# face_board.net
KiCad netlist of a schematic drawn in Altium Designer
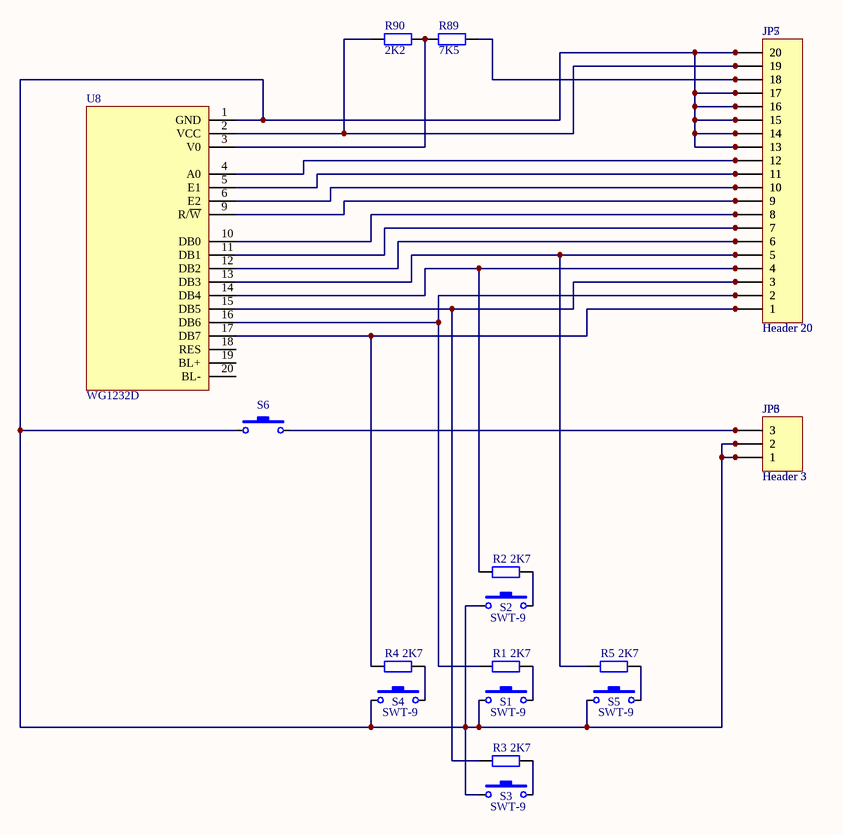
[diagram p0: face_board.SchDoc]

(export (version "E")
  (design (tool "Eeschema 10.0.6"))
  (components
    (comp (ref "JP3")
      (value "Header 3")
      (footprint "HDR1X3")
      (description "Header, 3-Pin")
      (fields (field (name "MANUFACTURER") "Generic Components") (field (name "PUBLISHER") "Altium Limited"))
      (libsource (lib "Miscellaneous Connectors") (part "Header 3"))
    )
    (comp (ref "JP5")
      (value "Header 20")
      (footprint "HDR1X20")
      (description "Header, 20-Pin")
      (fields (field (name "MANUFACTURER") "Generic Components") (field (name "PUBLISHER") "Altium Limited"))
      (libsource (lib "Miscellaneous Connectors") (part "Header 20"))
    )
    (comp (ref "JP6")
      (value "Header 3")
      (footprint "HDR1X3")
      (description "Header, 3-Pin")
      (fields (field (name "MANUFACTURER") "Generic Components") (field (name "PUBLISHER") "Altium Limited"))
      (libsource (lib "Miscellaneous Connectors") (part "Header 3"))
    )
    (comp (ref "JP7")
      (value "Header 20")
      (footprint "HDR1X20")
      (description "Header, 20-Pin")
      (fields (field (name "MANUFACTURER") "Generic Components") (field (name "PUBLISHER") "Altium Limited"))
      (libsource (lib "Miscellaneous Connectors") (part "Header 20"))
    )
    (comp (ref "R1")
      (value "2K7")
      (footprint "_1206")
      (description "Resistor")
      (fields (field (name "MANUFACTURER") "Generic Components") (field (name "PUBLISHER") "Altium Limited"))
      (libsource (lib "Miscellaneous Devices") (part "Res2"))
    )
    (comp (ref "R2")
      (value "2K7")
      (footprint "_1206")
      (description "Resistor")
      (fields (field (name "MANUFACTURER") "Generic Components") (field (name "PUBLISHER") "Altium Limited"))
      (libsource (lib "Miscellaneous Devices") (part "Res2"))
    )
    (comp (ref "R3")
      (value "2K7")
      (footprint "_1206")
      (description "Resistor")
      (fields (field (name "MANUFACTURER") "Generic Components") (field (name "PUBLISHER") "Altium Limited"))
      (libsource (lib "Miscellaneous Devices") (part "Res2"))
    )
    (comp (ref "R4")
      (value "2K7")
      (footprint "_1206")
      (description "Resistor")
      (fields (field (name "MANUFACTURER") "Generic Components") (field (name "PUBLISHER") "Altium Limited"))
      (libsource (lib "Miscellaneous Devices") (part "Res2"))
    )
    (comp (ref "R5")
      (value "2K7")
      (footprint "_1206")
      (description "Resistor")
      (fields (field (name "MANUFACTURER") "Generic Components") (field (name "PUBLISHER") "Altium Limited"))
      (libsource (lib "Miscellaneous Devices") (part "Res2"))
    )
    (comp (ref "R89")
      (value "7K5")
      (footprint "_1206")
      (description "Resistor")
      (fields (field (name "MANUFACTURER") "Generic Components") (field (name "PUBLISHER") "Altium Limited"))
      (libsource (lib "") (part "Res2_1"))
    )
    (comp (ref "R90")
      (value "2K2")
      (footprint "_1206")
      (description "Resistor")
      (fields (field (name "MANUFACTURER") "Generic Components") (field (name "PUBLISHER") "Altium Limited"))
      (libsource (lib "") (part "Res2_1"))
    )
    (comp (ref "S1")
      (value "SWT-9")
      (footprint "SWT-9")
      (description "Switch")
      (fields (field (name "MANUFACTURER") "Generic Components") (field (name "PUBLISHER") "Altium Limited"))
      (libsource (lib "PAL") (part "SWT-9"))
    )
    (comp (ref "S2")
      (value "SWT-9")
      (footprint "SWT-9")
      (description "Switch")
      (fields (field (name "MANUFACTURER") "Generic Components") (field (name "PUBLISHER") "Altium Limited"))
      (libsource (lib "PAL") (part "SWT-9"))
    )
    (comp (ref "S3")
      (value "SWT-9")
      (footprint "SWT-9")
      (description "Switch")
      (fields (field (name "MANUFACTURER") "Generic Components") (field (name "PUBLISHER") "Altium Limited"))
      (libsource (lib "PAL") (part "SWT-9"))
    )
    (comp (ref "S4")
      (value "SWT-9")
      (footprint "SWT-9")
      (description "Switch")
      (fields (field (name "MANUFACTURER") "Generic Components") (field (name "PUBLISHER") "Altium Limited"))
      (libsource (lib "PAL") (part "SWT-9"))
    )
    (comp (ref "S5")
      (value "SWT-9")
      (footprint "SWT-9")
      (description "Switch")
      (fields (field (name "MANUFACTURER") "Generic Components") (field (name "PUBLISHER") "Altium Limited"))
      (libsource (lib "PAL") (part "SWT-9"))
    )
    (comp (ref "S6")
      (value "SWT-6")
      (footprint "SWT-6")
      (description "Button")
      (fields (field (name "MANUFACTURER") "Generic Components") (field (name "PUBLISHER") "Altium Limited"))
      (libsource (lib "PAL") (part "SWT-9"))
    )
    (comp (ref "U8") (value "WG1232D") (footprint "WG1232D") (libsource (lib "PAL") (part "WG1232D_pereh")))
  )
  (nets
    (net (code "1") (name "Net-(JP3-Pad3)") (class "Default")
      (node (ref "JP3") (pin "3") (pinfunction "3_3") (pintype "passive"))
      (node (ref "JP6") (pin "3") (pinfunction "3_3") (pintype "passive"))
      (node (ref "S6") (pin "2") (pinfunction "2_2") (pintype "passive"))
    )
    (net (code "2") (name "Net-(JP5-Pad18)") (class "Default")
      (node (ref "JP5") (pin "18") (pinfunction "18_18") (pintype "passive"))
      (node (ref "JP7") (pin "18") (pinfunction "18_18") (pintype "passive"))
      (node (ref "R89") (pin "1") (pinfunction "1_1") (pintype "passive"))
    )
    (net (code "3") (name "Net-(R1-Pad1)") (class "Default")
      (node (ref "R1") (pin "1") (pinfunction "1_1") (pintype "passive"))
      (node (ref "S1") (pin "2") (pinfunction "2_2") (pintype "passive"))
    )
    (net (code "4") (name "Net-(R2-Pad1)") (class "Default")
      (node (ref "R2") (pin "1") (pinfunction "1_1") (pintype "passive"))
      (node (ref "S2") (pin "2") (pinfunction "2_2") (pintype "passive"))
    )
    (net (code "5") (name "Net-(R3-Pad1)") (class "Default")
      (node (ref "R3") (pin "1") (pinfunction "1_1") (pintype "passive"))
      (node (ref "S3") (pin "2") (pinfunction "2_2") (pintype "passive"))
    )
    (net (code "6") (name "Net-(R4-Pad1)") (class "Default")
      (node (ref "R4") (pin "1") (pinfunction "1_1") (pintype "passive"))
      (node (ref "S4") (pin "2") (pinfunction "2_2") (pintype "passive"))
    )
    (net (code "7") (name "Net-(R5-Pad1)") (class "Default")
      (node (ref "R5") (pin "1") (pinfunction "1_1") (pintype "passive"))
      (node (ref "S5") (pin "2") (pinfunction "2_2") (pintype "passive"))
    )
    (net (code "8") (name "Net-(U8-A0)") (class "Default")
      (node (ref "JP5") (pin "12") (pinfunction "12_12") (pintype "passive"))
      (node (ref "JP7") (pin "12") (pinfunction "12_12") (pintype "passive"))
      (node (ref "U8") (pin "4") (pinfunction "A0_4") (pintype "passive"))
    )
    (net (code "9") (name "Net-(U8-DB0)") (class "Default")
      (node (ref "JP5") (pin "8") (pinfunction "8_8") (pintype "passive"))
      (node (ref "JP7") (pin "8") (pinfunction "8_8") (pintype "passive"))
      (node (ref "U8") (pin "10") (pinfunction "DB0_10") (pintype "passive"))
    )
    (net (code "10") (name "Net-(U8-DB1)") (class "Default")
      (node (ref "JP5") (pin "7") (pinfunction "7_7") (pintype "passive"))
      (node (ref "JP7") (pin "7") (pinfunction "7_7") (pintype "passive"))
      (node (ref "U8") (pin "11") (pinfunction "DB1_11") (pintype "passive"))
    )
    (net (code "11") (name "Net-(U8-DB2)") (class "Default")
      (node (ref "JP5") (pin "6") (pinfunction "6_6") (pintype "passive"))
      (node (ref "JP7") (pin "6") (pinfunction "6_6") (pintype "passive"))
      (node (ref "U8") (pin "12") (pinfunction "DB2_12") (pintype "passive"))
    )
    (net (code "12") (name "Net-(U8-DB3)") (class "Default")
      (node (ref "JP5") (pin "5") (pinfunction "5_5") (pintype "passive"))
      (node (ref "JP7") (pin "5") (pinfunction "5_5") (pintype "passive"))
      (node (ref "R5") (pin "2") (pinfunction "2_2") (pintype "passive"))
      (node (ref "U8") (pin "13") (pinfunction "DB3_13") (pintype "passive"))
    )
    (net (code "13") (name "Net-(U8-DB4)") (class "Default")
      (node (ref "JP5") (pin "4") (pinfunction "4_4") (pintype "passive"))
      (node (ref "JP7") (pin "4") (pinfunction "4_4") (pintype "passive"))
      (node (ref "R2") (pin "2") (pinfunction "2_2") (pintype "passive"))
      (node (ref "U8") (pin "14") (pinfunction "DB4_14") (pintype "passive"))
    )
    (net (code "14") (name "Net-(U8-DB5)") (class "Default")
      (node (ref "JP5") (pin "3") (pinfunction "3_3") (pintype "passive"))
      (node (ref "JP7") (pin "3") (pinfunction "3_3") (pintype "passive"))
      (node (ref "R3") (pin "2") (pinfunction "2_2") (pintype "passive"))
      (node (ref "U8") (pin "15") (pinfunction "DB5_15") (pintype "passive"))
    )
    (net (code "15") (name "Net-(U8-DB6)") (class "Default")
      (node (ref "JP5") (pin "2") (pinfunction "2_2") (pintype "passive"))
      (node (ref "JP7") (pin "2") (pinfunction "2_2") (pintype "passive"))
      (node (ref "R1") (pin "2") (pinfunction "2_2") (pintype "passive"))
      (node (ref "U8") (pin "16") (pinfunction "DB6_16") (pintype "passive"))
    )
    (net (code "16") (name "Net-(U8-DB7)") (class "Default")
      (node (ref "JP5") (pin "1") (pinfunction "1_1") (pintype "passive"))
      (node (ref "JP7") (pin "1") (pinfunction "1_1") (pintype "passive"))
      (node (ref "R4") (pin "2") (pinfunction "2_2") (pintype "passive"))
      (node (ref "U8") (pin "17") (pinfunction "DB7_17") (pintype "passive"))
    )
    (net (code "17") (name "Net-(U8-E1)") (class "Default")
      (node (ref "JP5") (pin "11") (pinfunction "11_11") (pintype "passive"))
      (node (ref "JP7") (pin "11") (pinfunction "11_11") (pintype "passive"))
      (node (ref "U8") (pin "5") (pinfunction "E1_5") (pintype "passive"))
    )
    (net (code "18") (name "Net-(U8-E2)") (class "Default")
      (node (ref "JP5") (pin "10") (pinfunction "10_10") (pintype "passive"))
      (node (ref "JP7") (pin "10") (pinfunction "10_10") (pintype "passive"))
      (node (ref "U8") (pin "6") (pinfunction "E2_6") (pintype "passive"))
    )
    (net (code "19") (name "Net-(U8-GND)") (class "Default")
      (node (ref "JP3") (pin "1") (pinfunction "1_1") (pintype "passive"))
      (node (ref "JP3") (pin "2") (pinfunction "2_2") (pintype "passive"))
      (node (ref "JP5") (pin "13") (pinfunction "13_13") (pintype "passive"))
      (node (ref "JP5") (pin "14") (pinfunction "14_14") (pintype "passive"))
      (node (ref "JP5") (pin "15") (pinfunction "15_15") (pintype "passive"))
      (node (ref "JP5") (pin "16") (pinfunction "16_16") (pintype "passive"))
      (node (ref "JP5") (pin "17") (pinfunction "17_17") (pintype "passive"))
      (node (ref "JP5") (pin "20") (pinfunction "20_20") (pintype "passive"))
      (node (ref "JP6") (pin "1") (pinfunction "1_1") (pintype "passive"))
      (node (ref "JP6") (pin "2") (pinfunction "2_2") (pintype "passive"))
      (node (ref "JP7") (pin "13") (pinfunction "13_13") (pintype "passive"))
      (node (ref "JP7") (pin "14") (pinfunction "14_14") (pintype "passive"))
      (node (ref "JP7") (pin "15") (pinfunction "15_15") (pintype "passive"))
      (node (ref "JP7") (pin "16") (pinfunction "16_16") (pintype "passive"))
      (node (ref "JP7") (pin "17") (pinfunction "17_17") (pintype "passive"))
      (node (ref "JP7") (pin "20") (pinfunction "20_20") (pintype "passive"))
      (node (ref "S1") (pin "1") (pinfunction "1_1") (pintype "passive"))
      (node (ref "S2") (pin "1") (pinfunction "1_1") (pintype "passive"))
      (node (ref "S3") (pin "1") (pinfunction "1_1") (pintype "passive"))
      (node (ref "S4") (pin "1") (pinfunction "1_1") (pintype "passive"))
      (node (ref "S5") (pin "1") (pinfunction "1_1") (pintype "passive"))
      (node (ref "S6") (pin "1") (pinfunction "1_1") (pintype "passive"))
      (node (ref "U8") (pin "1") (pinfunction "GND_1") (pintype "passive"))
    )
    (net (code "20") (name "Net-(U8-R{slash}~{W})") (class "Default")
      (node (ref "JP5") (pin "9") (pinfunction "9_9") (pintype "passive"))
      (node (ref "JP7") (pin "9") (pinfunction "9_9") (pintype "passive"))
      (node (ref "U8") (pin "9") (pinfunction "R/~{W}_9") (pintype "passive"))
    )
    (net (code "21") (name "Net-(U8-V0)") (class "Default")
      (node (ref "R89") (pin "2") (pinfunction "2_2") (pintype "passive"))
      (node (ref "R90") (pin "1") (pinfunction "1_1") (pintype "passive"))
      (node (ref "U8") (pin "3") (pinfunction "V0_3") (pintype "passive"))
    )
    (net (code "22") (name "Net-(U8-VCC)") (class "Default")
      (node (ref "JP5") (pin "19") (pinfunction "19_19") (pintype "passive"))
      (node (ref "JP7") (pin "19") (pinfunction "19_19") (pintype "passive"))
      (node (ref "R90") (pin "2") (pinfunction "2_2") (pintype "passive"))
      (node (ref "U8") (pin "2") (pinfunction "VCC_2") (pintype "passive"))
    )
    (net (code "23") (name "unconnected-(U8-BL+-Pad19)") (class "Default")
      (node (ref "U8") (pin "19") (pinfunction "BL+_19") (pintype "passive"))
    )
    (net (code "24") (name "unconnected-(U8-BL--Pad20)") (class "Default")
      (node (ref "U8") (pin "20") (pinfunction "BL-_20") (pintype "passive"))
    )
    (net (code "25") (name "unconnected-(U8-RES-Pad18)") (class "Default")
      (node (ref "U8") (pin "18") (pinfunction "RES_18") (pintype "passive"))
    )
  )
)
